# v0_1.net
KiCad netlist of a schematic drawn in EAGLE
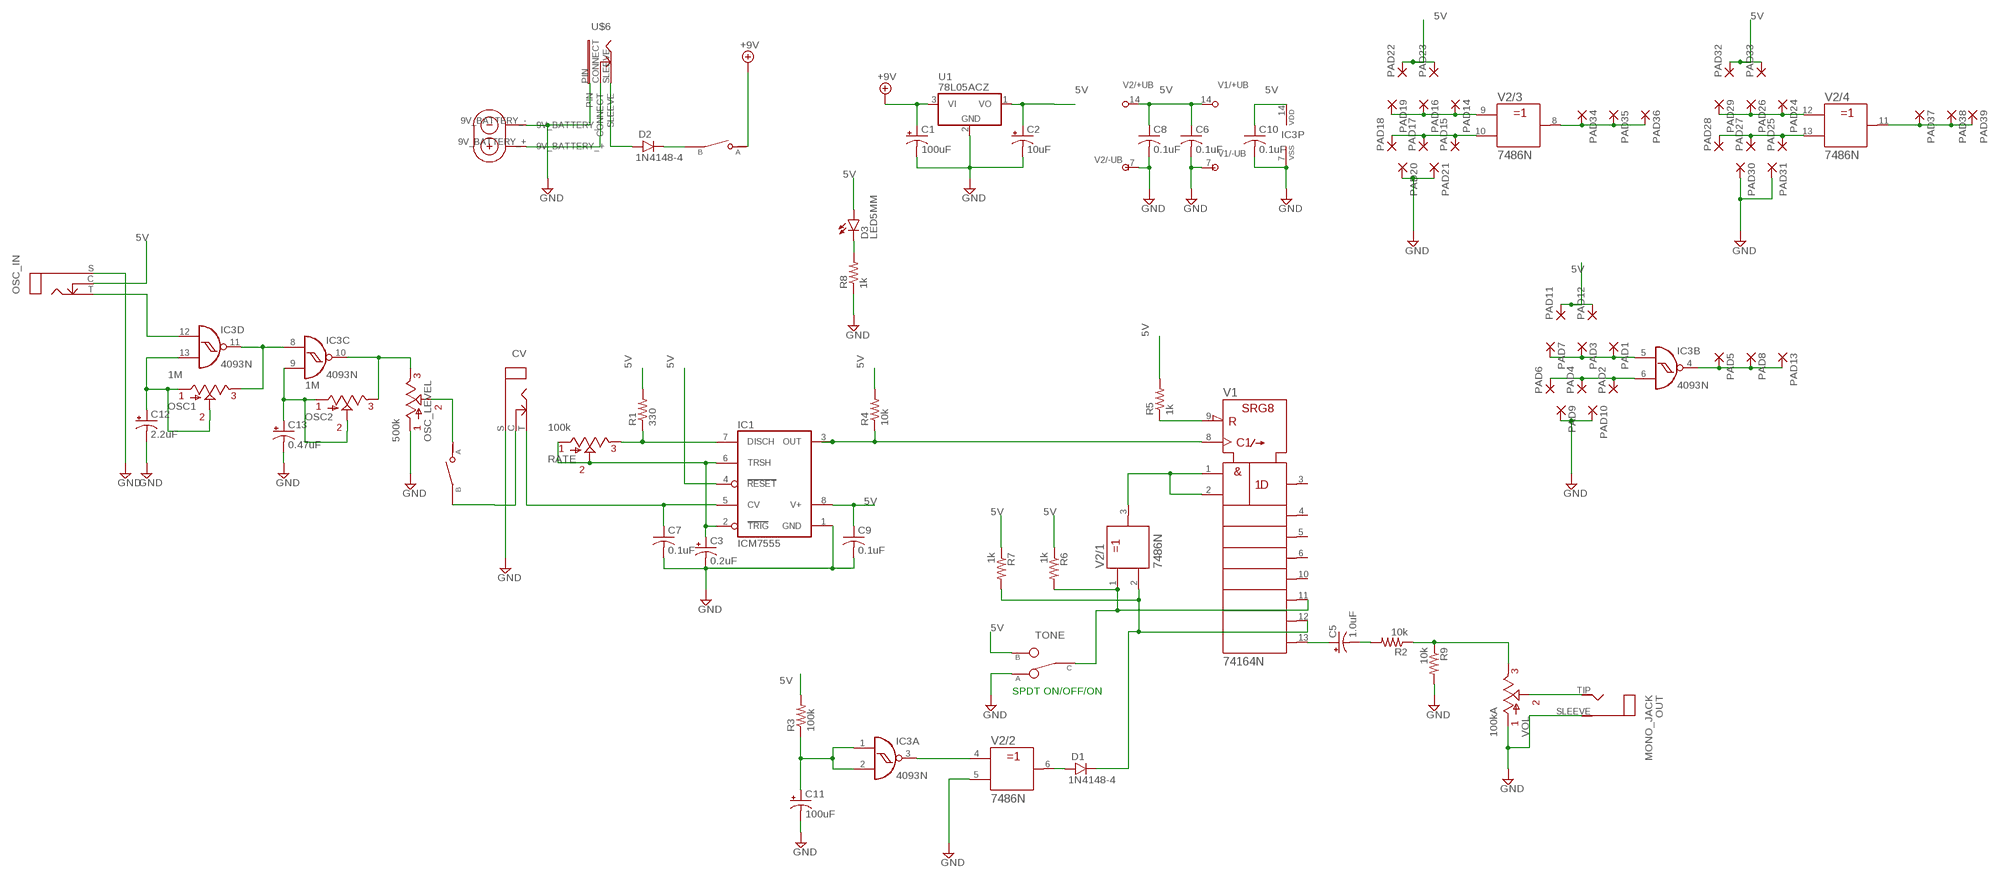
[diagram p0: schematic, sheet 1]

(export (version "E")
  (design (tool "Eeschema 10.0.6"))
  (components
    (comp (ref "C1")
      (value "100uF")
      (footprint "eagle-import:063_025")
      (libsource (lib "eagle-import") (part "0631"))
    )
    (comp (ref "C2")
      (value "10uF")
      (footprint "eagle-import:063_025")
      (libsource (lib "eagle-import") (part "0631"))
    )
    (comp (ref "C3")
      (value "0.2uF")
      (footprint "eagle-import:063_025")
      (libsource (lib "eagle-import") (part "0631"))
    )
    (comp (ref "C5")
      (value "1.0uF")
      (footprint "eagle-import:063_025")
      (libsource (lib "eagle-import") (part "0631"))
    )
    (comp (ref "C6")
      (value "0.1uF")
      (footprint "eagle-import:C050-030X075")
      (libsource (lib "eagle-import") (part "C-US050-030X075"))
    )
    (comp (ref "C7")
      (value "0.1uF")
      (footprint "eagle-import:C050-030X075")
      (libsource (lib "eagle-import") (part "C-US050-030X075"))
    )
    (comp (ref "C8")
      (value "0.1uF")
      (footprint "eagle-import:C050-030X075")
      (libsource (lib "eagle-import") (part "C-US050-030X075"))
    )
    (comp (ref "C9")
      (value "0.1uF")
      (footprint "eagle-import:C050-030X075")
      (libsource (lib "eagle-import") (part "C-US050-030X075"))
    )
    (comp (ref "C10")
      (value "0.1uF")
      (footprint "eagle-import:C050-030X075")
      (libsource (lib "eagle-import") (part "C-US050-030X075"))
    )
    (comp (ref "C11")
      (value "100uF")
      (footprint "eagle-import:063_025")
      (libsource (lib "eagle-import") (part "0631"))
    )
    (comp (ref "C12")
      (value "2.2uF")
      (footprint "eagle-import:063_025")
      (libsource (lib "eagle-import") (part "0631"))
    )
    (comp (ref "C13")
      (value "0.47uF")
      (footprint "eagle-import:063_025")
      (libsource (lib "eagle-import") (part "0631"))
    )
    (comp (ref "CV")
      (value "MONO_JACK_W_SHUNT")
      (footprint "eagle-import:MONO_JACK_W_SHUNT")
      (libsource (lib "eagle-import") (part "MONO_JACK_W_SHUNT"))
    )
    (comp (ref "CV+OSC_ON/OFF")
      (value "SPST_SWITCH")
      (footprint "eagle-import:SPST_TOGGLE_SWITCH")
      (libsource (lib "eagle-import") (part "SPST_SWITCH"))
    )
    (comp (ref "D1")
      (value "1N4148-4")
      (footprint "eagle-import:DO35-4")
      (libsource (lib "eagle-import") (part "1N4148-4"))
    )
    (comp (ref "D2")
      (value "1N4148-4")
      (footprint "eagle-import:DO35-4")
      (libsource (lib "eagle-import") (part "1N4148-4"))
    )
    (comp (ref "D3")
      (value "LED5MM")
      (footprint "eagle-import:LED5MM")
      (libsource (lib "eagle-import") (part "LED5MM"))
    )
    (comp (ref "IC1")
      (value "ICM7555")
      (footprint "eagle-import:DIL08")
      (libsource (lib "eagle-import") (part "ICM7555"))
    )
    (comp (ref "IC3")
      (value "4093N")
      (footprint "eagle-import:DIL14")
      (libsource (lib "eagle-import") (part "4093N"))
    )
    (comp (ref "ON/OFF")
      (value "SPST_SWITCH")
      (footprint "eagle-import:SPST_TOGGLE_SWITCH")
      (libsource (lib "eagle-import") (part "SPST_SWITCH"))
    )
    (comp (ref "OSC1")
      (value "1M")
      (footprint "eagle-import:POT")
      (libsource (lib "eagle-import") (part "POT"))
    )
    (comp (ref "OSC2")
      (value "1M")
      (footprint "eagle-import:POT")
      (libsource (lib "eagle-import") (part "POT"))
    )
    (comp (ref "OSC_IN")
      (value "MONO_JACK_W_SHUNT")
      (footprint "eagle-import:MONO_JACK_W_SHUNT")
      (libsource (lib "eagle-import") (part "MONO_JACK_W_SHUNT"))
    )
    (comp (ref "OSC_LEVEL")
      (value "500k")
      (footprint "eagle-import:POT")
      (libsource (lib "eagle-import") (part "POT"))
    )
    (comp (ref "OUT")
      (value "MONO_JACK")
      (footprint "eagle-import:MONO_JACK")
      (libsource (lib "eagle-import") (part "MONO_JACK"))
    )
    (comp (ref "PAD1")
      (value "WIREPAD1,6/0,9")
      (footprint "eagle-import:1,6_0,9")
      (libsource (lib "eagle-import") (part "WIREPAD1,6/0,9"))
    )
    (comp (ref "PAD2")
      (value "WIREPAD1,6/0,9")
      (footprint "eagle-import:1,6_0,9")
      (libsource (lib "eagle-import") (part "WIREPAD1,6/0,9"))
    )
    (comp (ref "PAD3")
      (value "WIREPAD1,6/0,9")
      (footprint "eagle-import:1,6_0,9")
      (libsource (lib "eagle-import") (part "WIREPAD1,6/0,9"))
    )
    (comp (ref "PAD4")
      (value "WIREPAD1,6/0,9")
      (footprint "eagle-import:1,6_0,9")
      (libsource (lib "eagle-import") (part "WIREPAD1,6/0,9"))
    )
    (comp (ref "PAD5")
      (value "WIREPAD1,6/0,9")
      (footprint "eagle-import:1,6_0,9")
      (libsource (lib "eagle-import") (part "WIREPAD1,6/0,9"))
    )
    (comp (ref "PAD6")
      (value "WIREPAD1,6/0,9")
      (footprint "eagle-import:1,6_0,9")
      (libsource (lib "eagle-import") (part "WIREPAD1,6/0,9"))
    )
    (comp (ref "PAD7")
      (value "WIREPAD1,6/0,9")
      (footprint "eagle-import:1,6_0,9")
      (libsource (lib "eagle-import") (part "WIREPAD1,6/0,9"))
    )
    (comp (ref "PAD8")
      (value "WIREPAD1,6/0,9")
      (footprint "eagle-import:1,6_0,9")
      (libsource (lib "eagle-import") (part "WIREPAD1,6/0,9"))
    )
    (comp (ref "PAD9")
      (value "WIREPAD1,6/0,9")
      (footprint "eagle-import:1,6_0,9")
      (libsource (lib "eagle-import") (part "WIREPAD1,6/0,9"))
    )
    (comp (ref "PAD10")
      (value "WIREPAD1,6/0,9")
      (footprint "eagle-import:1,6_0,9")
      (libsource (lib "eagle-import") (part "WIREPAD1,6/0,9"))
    )
    (comp (ref "PAD11")
      (value "WIREPAD1,6/0,9")
      (footprint "eagle-import:1,6_0,9")
      (libsource (lib "eagle-import") (part "WIREPAD1,6/0,9"))
    )
    (comp (ref "PAD12")
      (value "WIREPAD1,6/0,9")
      (footprint "eagle-import:1,6_0,9")
      (libsource (lib "eagle-import") (part "WIREPAD1,6/0,9"))
    )
    (comp (ref "PAD13")
      (value "WIREPAD1,6/0,9")
      (footprint "eagle-import:1,6_0,9")
      (libsource (lib "eagle-import") (part "WIREPAD1,6/0,9"))
    )
    (comp (ref "PAD14")
      (value "WIREPAD1,6/0,9")
      (footprint "eagle-import:1,6_0,9")
      (libsource (lib "eagle-import") (part "WIREPAD1,6/0,9"))
    )
    (comp (ref "PAD15")
      (value "WIREPAD1,6/0,9")
      (footprint "eagle-import:1,6_0,9")
      (libsource (lib "eagle-import") (part "WIREPAD1,6/0,9"))
    )
    (comp (ref "PAD16")
      (value "WIREPAD1,6/0,9")
      (footprint "eagle-import:1,6_0,9")
      (libsource (lib "eagle-import") (part "WIREPAD1,6/0,9"))
    )
    (comp (ref "PAD17")
      (value "WIREPAD1,6/0,9")
      (footprint "eagle-import:1,6_0,9")
      (libsource (lib "eagle-import") (part "WIREPAD1,6/0,9"))
    )
    (comp (ref "PAD18")
      (value "WIREPAD1,6/0,9")
      (footprint "eagle-import:1,6_0,9")
      (libsource (lib "eagle-import") (part "WIREPAD1,6/0,9"))
    )
    (comp (ref "PAD19")
      (value "WIREPAD1,6/0,9")
      (footprint "eagle-import:1,6_0,9")
      (libsource (lib "eagle-import") (part "WIREPAD1,6/0,9"))
    )
    (comp (ref "PAD20")
      (value "WIREPAD1,6/0,9")
      (footprint "eagle-import:1,6_0,9")
      (libsource (lib "eagle-import") (part "WIREPAD1,6/0,9"))
    )
    (comp (ref "PAD21")
      (value "WIREPAD1,6/0,9")
      (footprint "eagle-import:1,6_0,9")
      (libsource (lib "eagle-import") (part "WIREPAD1,6/0,9"))
    )
    (comp (ref "PAD22")
      (value "WIREPAD1,6/0,9")
      (footprint "eagle-import:1,6_0,9")
      (libsource (lib "eagle-import") (part "WIREPAD1,6/0,9"))
    )
    (comp (ref "PAD23")
      (value "WIREPAD1,6/0,9")
      (footprint "eagle-import:1,6_0,9")
      (libsource (lib "eagle-import") (part "WIREPAD1,6/0,9"))
    )
    (comp (ref "PAD24")
      (value "WIREPAD1,6/0,9")
      (footprint "eagle-import:1,6_0,9")
      (libsource (lib "eagle-import") (part "WIREPAD1,6/0,9"))
    )
    (comp (ref "PAD25")
      (value "WIREPAD1,6/0,9")
      (footprint "eagle-import:1,6_0,9")
      (libsource (lib "eagle-import") (part "WIREPAD1,6/0,9"))
    )
    (comp (ref "PAD26")
      (value "WIREPAD1,6/0,9")
      (footprint "eagle-import:1,6_0,9")
      (libsource (lib "eagle-import") (part "WIREPAD1,6/0,9"))
    )
    (comp (ref "PAD27")
      (value "WIREPAD1,6/0,9")
      (footprint "eagle-import:1,6_0,9")
      (libsource (lib "eagle-import") (part "WIREPAD1,6/0,9"))
    )
    (comp (ref "PAD28")
      (value "WIREPAD1,6/0,9")
      (footprint "eagle-import:1,6_0,9")
      (libsource (lib "eagle-import") (part "WIREPAD1,6/0,9"))
    )
    (comp (ref "PAD29")
      (value "WIREPAD1,6/0,9")
      (footprint "eagle-import:1,6_0,9")
      (libsource (lib "eagle-import") (part "WIREPAD1,6/0,9"))
    )
    (comp (ref "PAD30")
      (value "WIREPAD1,6/0,9")
      (footprint "eagle-import:1,6_0,9")
      (libsource (lib "eagle-import") (part "WIREPAD1,6/0,9"))
    )
    (comp (ref "PAD31")
      (value "WIREPAD1,6/0,9")
      (footprint "eagle-import:1,6_0,9")
      (libsource (lib "eagle-import") (part "WIREPAD1,6/0,9"))
    )
    (comp (ref "PAD32")
      (value "WIREPAD1,6/0,9")
      (footprint "eagle-import:1,6_0,9")
      (libsource (lib "eagle-import") (part "WIREPAD1,6/0,9"))
    )
    (comp (ref "PAD33")
      (value "WIREPAD1,6/0,9")
      (footprint "eagle-import:1,6_0,9")
      (libsource (lib "eagle-import") (part "WIREPAD1,6/0,9"))
    )
    (comp (ref "PAD34")
      (value "WIREPAD1,6/0,9")
      (footprint "eagle-import:1,6_0,9")
      (libsource (lib "eagle-import") (part "WIREPAD1,6/0,9"))
    )
    (comp (ref "PAD35")
      (value "WIREPAD1,6/0,9")
      (footprint "eagle-import:1,6_0,9")
      (libsource (lib "eagle-import") (part "WIREPAD1,6/0,9"))
    )
    (comp (ref "PAD36")
      (value "WIREPAD1,6/0,9")
      (footprint "eagle-import:1,6_0,9")
      (libsource (lib "eagle-import") (part "WIREPAD1,6/0,9"))
    )
    (comp (ref "PAD37")
      (value "WIREPAD1,6/0,9")
      (footprint "eagle-import:1,6_0,9")
      (libsource (lib "eagle-import") (part "WIREPAD1,6/0,9"))
    )
    (comp (ref "PAD38")
      (value "WIREPAD1,6/0,9")
      (footprint "eagle-import:1,6_0,9")
      (libsource (lib "eagle-import") (part "WIREPAD1,6/0,9"))
    )
    (comp (ref "PAD39")
      (value "WIREPAD1,6/0,9")
      (footprint "eagle-import:1,6_0,9")
      (libsource (lib "eagle-import") (part "WIREPAD1,6/0,9"))
    )
    (comp (ref "R1")
      (value "330")
      (footprint "eagle-import:R0207_4")
      (libsource (lib "eagle-import") (part "6MM.4"))
    )
    (comp (ref "R2")
      (value "10k")
      (footprint "eagle-import:R0207_4")
      (libsource (lib "eagle-import") (part "6MM.4"))
    )
    (comp (ref "R3")
      (value "100k")
      (footprint "eagle-import:R0207_4")
      (libsource (lib "eagle-import") (part "6MM.4"))
    )
    (comp (ref "R4")
      (value "10k")
      (footprint "eagle-import:R0207_4")
      (libsource (lib "eagle-import") (part "6MM.4"))
    )
    (comp (ref "R5")
      (value "1k")
      (footprint "eagle-import:R0207_4")
      (libsource (lib "eagle-import") (part "6MM.4"))
    )
    (comp (ref "R6")
      (value "1k")
      (footprint "eagle-import:R0207_4")
      (libsource (lib "eagle-import") (part "6MM.4"))
    )
    (comp (ref "R7")
      (value "1k")
      (footprint "eagle-import:R0207_4")
      (libsource (lib "eagle-import") (part "6MM.4"))
    )
    (comp (ref "R8")
      (value "1k")
      (footprint "eagle-import:R0207_4")
      (libsource (lib "eagle-import") (part "6MM.4"))
    )
    (comp (ref "R9")
      (value "10k")
      (footprint "eagle-import:R0207_4")
      (libsource (lib "eagle-import") (part "6MM.4"))
    )
    (comp (ref "RATE")
      (value "100k")
      (footprint "eagle-import:POT")
      (libsource (lib "eagle-import") (part "POT"))
    )
    (comp (ref "TONE")
      (value "SPDT_SWITCH")
      (footprint "eagle-import:SPDT_TOGGLE_SWITCH")
      (libsource (lib "eagle-import") (part "SPDT_SWITCH"))
    )
    (comp (ref "U$6")
      (value "DC_JACK_OFFBOARD")
      (footprint "eagle-import:DC_JACK_OFFBOARD")
      (libsource (lib "eagle-import") (part "DC_JACK_OFFBOARD"))
    )
    (comp (ref "U$7")
      (value "9V_BATTERY_CLIP")
      (footprint "eagle-import:9V_BATTERY")
      (libsource (lib "eagle-import") (part "9V_BATTERY_CLIP"))
    )
    (comp (ref "U1")
      (value "78L05ACZ")
      (footprint "eagle-import:TO-92")
      (libsource (lib "eagle-import") (part "78L05ACZ"))
    )
    (comp (ref "V1")
      (value "74164N")
      (footprint "eagle-import:DIL14")
      (libsource (lib "eagle-import") (part "74164N"))
    )
    (comp (ref "V2")
      (value "7486N")
      (footprint "eagle-import:DIL14")
      (libsource (lib "eagle-import") (part "7486N"))
    )
    (comp (ref "VOL")
      (value "100kA")
      (footprint "eagle-import:POT")
      (libsource (lib "eagle-import") (part "POT"))
    )
  )
  (nets
    (net (code "1") (name "+9V") (class "Default")
      (node (ref "C1") (pin "+") (pinfunction "+_+") (pintype "passive"))
      (node (ref "ON/OFF") (pin "A") (pinfunction "A_A") (pintype "passive"))
      (node (ref "U1") (pin "3") (pinfunction "VI_3") (pintype "input"))
    )
    (net (code "2") (name "/5V") (class "Default")
      (node (ref "C10") (pin "1") (pinfunction "1_1") (pintype "passive"))
      (node (ref "C2") (pin "+") (pinfunction "+_+") (pintype "passive"))
      (node (ref "C6") (pin "1") (pinfunction "1_1") (pintype "passive"))
      (node (ref "C8") (pin "1") (pinfunction "1_1") (pintype "passive"))
      (node (ref "C9") (pin "1") (pinfunction "1_1") (pintype "passive"))
      (node (ref "D3") (pin "A") (pinfunction "A_A") (pintype "passive"))
      (node (ref "IC1") (pin "4") (pinfunction "RESET_4") (pintype "input"))
      (node (ref "IC1") (pin "8") (pinfunction "V+_8") (pintype "power_in"))
      (node (ref "IC3") (pin "14") (pinfunction "VDD_14") (pintype "power_in"))
      (node (ref "OSC_IN") (pin "C") (pinfunction "CONNECT_C") (pintype "passive"))
      (node (ref "PAD11") (pin "1") (pinfunction "P_1") (pintype "passive"))
      (node (ref "PAD12") (pin "1") (pinfunction "P_1") (pintype "passive"))
      (node (ref "PAD22") (pin "1") (pinfunction "P_1") (pintype "passive"))
      (node (ref "PAD23") (pin "1") (pinfunction "P_1") (pintype "passive"))
      (node (ref "PAD32") (pin "1") (pinfunction "P_1") (pintype "passive"))
      (node (ref "PAD33") (pin "1") (pinfunction "P_1") (pintype "passive"))
      (node (ref "R1") (pin "2") (pinfunction "2_2") (pintype "passive"))
      (node (ref "R3") (pin "2") (pinfunction "2_2") (pintype "passive"))
      (node (ref "R4") (pin "2") (pinfunction "2_2") (pintype "passive"))
      (node (ref "R5") (pin "2") (pinfunction "2_2") (pintype "passive"))
      (node (ref "R6") (pin "1") (pinfunction "1_1") (pintype "passive"))
      (node (ref "R7") (pin "1") (pinfunction "1_1") (pintype "passive"))
      (node (ref "TONE") (pin "B") (pinfunction "B_B") (pintype "passive"))
      (node (ref "U1") (pin "1") (pinfunction "VO_1") (pintype "passive"))
      (node (ref "V1") (pin "14") (pinfunction "+UB_14") (pintype "power_in"))
      (node (ref "V2") (pin "14") (pinfunction "+UB_14") (pintype "power_in"))
    )
    (net (code "3") (name "GND") (class "Default")
      (node (ref "C1") (pin "-") (pinfunction "-_-") (pintype "passive"))
      (node (ref "C10") (pin "2") (pinfunction "2_2") (pintype "passive"))
      (node (ref "C11") (pin "-") (pinfunction "-_-") (pintype "passive"))
      (node (ref "C12") (pin "-") (pinfunction "-_-") (pintype "passive"))
      (node (ref "C13") (pin "-") (pinfunction "-_-") (pintype "passive"))
      (node (ref "C2") (pin "-") (pinfunction "-_-") (pintype "passive"))
      (node (ref "C3") (pin "-") (pinfunction "-_-") (pintype "passive"))
      (node (ref "C6") (pin "2") (pinfunction "2_2") (pintype "passive"))
      (node (ref "C7") (pin "2") (pinfunction "2_2") (pintype "passive"))
      (node (ref "C8") (pin "2") (pinfunction "2_2") (pintype "passive"))
      (node (ref "C9") (pin "2") (pinfunction "2_2") (pintype "passive"))
      (node (ref "CV") (pin "S") (pinfunction "SLEEVE_S") (pintype "passive"))
      (node (ref "IC1") (pin "1") (pinfunction "GND_1") (pintype "power_in"))
      (node (ref "IC3") (pin "7") (pinfunction "VSS_7") (pintype "power_in"))
      (node (ref "OSC_IN") (pin "S") (pinfunction "SLEEVE_S") (pintype "passive"))
      (node (ref "OSC_LEVEL") (pin "1") (pinfunction "1_1") (pintype "passive"))
      (node (ref "OUT") (pin "SLEEVE") (pinfunction "SLEEVE_SLEEVE") (pintype "passive"))
      (node (ref "PAD10") (pin "1") (pinfunction "P_1") (pintype "passive"))
      (node (ref "PAD20") (pin "1") (pinfunction "P_1") (pintype "passive"))
      (node (ref "PAD21") (pin "1") (pinfunction "P_1") (pintype "passive"))
      (node (ref "PAD30") (pin "1") (pinfunction "P_1") (pintype "passive"))
      (node (ref "PAD31") (pin "1") (pinfunction "P_1") (pintype "passive"))
      (node (ref "PAD9") (pin "1") (pinfunction "P_1") (pintype "passive"))
      (node (ref "R8") (pin "1") (pinfunction "1_1") (pintype "passive"))
      (node (ref "R9") (pin "2") (pinfunction "2_2") (pintype "passive"))
      (node (ref "TONE") (pin "A") (pinfunction "A_A") (pintype "passive"))
      (node (ref "U$6") (pin "PIN") (pinfunction "PIN_PIN") (pintype "bidirectional"))
      (node (ref "U$7") (pin "9V_BATTERY_-") (pinfunction "9V_BATTERY_-_9V_BATTERY_-") (pintype "power_in"))
      (node (ref "U1") (pin "2") (pinfunction "GND_2") (pintype "passive"))
      (node (ref "V1") (pin "7") (pinfunction "-UB_7") (pintype "power_in"))
      (node (ref "V2") (pin "5") (pinfunction "B_5") (pintype "input"))
      (node (ref "V2") (pin "7") (pinfunction "-UB_7") (pintype "power_in"))
      (node (ref "VOL") (pin "1") (pinfunction "1_1") (pintype "passive"))
    )
    (net (code "4") (name "Net-(C5-Pad-)") (class "Default")
      (node (ref "C5") (pin "-") (pinfunction "-_-") (pintype "passive"))
      (node (ref "R2") (pin "2") (pinfunction "2_2") (pintype "passive"))
    )
    (net (code "5") (name "Net-(CV+OSC_ON/OFF-PadA)") (class "Default")
      (node (ref "CV+OSC_ON/OFF") (pin "A") (pinfunction "A_A") (pintype "passive"))
      (node (ref "OSC_LEVEL") (pin "2") (pinfunction "2_2") (pintype "passive"))
    )
    (net (code "6") (name "Net-(CV-CONNECT)") (class "Default")
      (node (ref "CV") (pin "C") (pinfunction "CONNECT_C") (pintype "passive"))
      (node (ref "CV+OSC_ON/OFF") (pin "B") (pinfunction "B_B") (pintype "passive"))
    )
    (net (code "7") (name "Net-(CV-TIP)") (class "Default")
      (node (ref "C7") (pin "1") (pinfunction "1_1") (pintype "passive"))
      (node (ref "CV") (pin "T") (pinfunction "TIP_T") (pintype "passive"))
      (node (ref "IC1") (pin "5") (pinfunction "CV_5") (pintype "passive"))
    )
    (net (code "8") (name "Net-(D2-PadA)") (class "Default")
      (node (ref "D2") (pin "A") (pinfunction "A_A") (pintype "passive"))
      (node (ref "U$6") (pin "SLEEVE") (pinfunction "SLEEVE_SLEEVE") (pintype "bidirectional"))
    )
    (net (code "9") (name "Net-(D2-PadC)") (class "Default")
      (node (ref "D2") (pin "C") (pinfunction "C_C") (pintype "passive"))
      (node (ref "ON/OFF") (pin "B") (pinfunction "B_B") (pintype "passive"))
    )
    (net (code "10") (name "Net-(D3-C)") (class "Default")
      (node (ref "D3") (pin "K") (pinfunction "C_K") (pintype "passive"))
      (node (ref "R8") (pin "2") (pinfunction "2_2") (pintype "passive"))
    )
    (net (code "11") (name "Net-(IC1-DISCH)") (class "Default")
      (node (ref "IC1") (pin "7") (pinfunction "DISCH_7") (pintype "input"))
      (node (ref "R1") (pin "1") (pinfunction "1_1") (pintype "passive"))
      (node (ref "RATE") (pin "3") (pinfunction "3_3") (pintype "passive"))
    )
    (net (code "12") (name "Net-(IC1-OUT)") (class "Default")
      (node (ref "IC1") (pin "3") (pinfunction "OUT_3") (pintype "output"))
      (node (ref "R4") (pin "1") (pinfunction "1_1") (pintype "passive"))
      (node (ref "V1") (pin "8") (pinfunction "CLK_8") (pintype "input"))
    )
    (net (code "13") (name "Net-(IC1-TRIG)") (class "Default")
      (node (ref "C3") (pin "+") (pinfunction "+_+") (pintype "passive"))
      (node (ref "IC1") (pin "2") (pinfunction "TRIG_2") (pintype "bidirectional"))
      (node (ref "IC1") (pin "6") (pinfunction "TRSH_6") (pintype "input"))
      (node (ref "RATE") (pin "1") (pinfunction "1_1") (pintype "passive"))
      (node (ref "RATE") (pin "2") (pinfunction "2_2") (pintype "passive"))
    )
    (net (code "14") (name "Net-(IC3A-I0)") (class "Default")
      (node (ref "C11") (pin "+") (pinfunction "+_+") (pintype "passive"))
      (node (ref "IC3") (pin "1") (pinfunction "I0_1") (pintype "input"))
      (node (ref "IC3") (pin "2") (pinfunction "I1_2") (pintype "input"))
      (node (ref "R3") (pin "1") (pinfunction "1_1") (pintype "passive"))
    )
    (net (code "15") (name "Net-(IC3A-O)") (class "Default")
      (node (ref "IC3") (pin "3") (pinfunction "O_3") (pintype "output"))
      (node (ref "V2") (pin "4") (pinfunction "A_4") (pintype "input"))
    )
    (net (code "16") (name "Net-(IC3B-I0)") (class "Default")
      (node (ref "IC3") (pin "5") (pinfunction "I0_5") (pintype "input"))
      (node (ref "PAD1") (pin "1") (pinfunction "P_1") (pintype "passive"))
      (node (ref "PAD3") (pin "1") (pinfunction "P_1") (pintype "passive"))
      (node (ref "PAD7") (pin "1") (pinfunction "P_1") (pintype "passive"))
    )
    (net (code "17") (name "Net-(IC3B-I1)") (class "Default")
      (node (ref "IC3") (pin "6") (pinfunction "I1_6") (pintype "input"))
      (node (ref "PAD2") (pin "1") (pinfunction "P_1") (pintype "passive"))
      (node (ref "PAD4") (pin "1") (pinfunction "P_1") (pintype "passive"))
      (node (ref "PAD6") (pin "1") (pinfunction "P_1") (pintype "passive"))
    )
    (net (code "18") (name "Net-(IC3B-O)") (class "Default")
      (node (ref "IC3") (pin "4") (pinfunction "O_4") (pintype "output"))
      (node (ref "PAD13") (pin "1") (pinfunction "P_1") (pintype "passive"))
      (node (ref "PAD5") (pin "1") (pinfunction "P_1") (pintype "passive"))
      (node (ref "PAD8") (pin "1") (pinfunction "P_1") (pintype "passive"))
    )
    (net (code "19") (name "Net-(IC3C-I0)") (class "Default")
      (node (ref "IC3") (pin "11") (pinfunction "O_11") (pintype "output"))
      (node (ref "IC3") (pin "8") (pinfunction "I0_8") (pintype "input"))
      (node (ref "OSC1") (pin "3") (pinfunction "3_3") (pintype "passive"))
    )
    (net (code "20") (name "Net-(IC3C-I1)") (class "Default")
      (node (ref "C13") (pin "+") (pinfunction "+_+") (pintype "passive"))
      (node (ref "IC3") (pin "9") (pinfunction "I1_9") (pintype "input"))
      (node (ref "OSC2") (pin "1") (pinfunction "1_1") (pintype "passive"))
      (node (ref "OSC2") (pin "2") (pinfunction "2_2") (pintype "passive"))
    )
    (net (code "21") (name "Net-(IC3C-O)") (class "Default")
      (node (ref "IC3") (pin "10") (pinfunction "O_10") (pintype "output"))
      (node (ref "OSC2") (pin "3") (pinfunction "3_3") (pintype "passive"))
      (node (ref "OSC_LEVEL") (pin "3") (pinfunction "3_3") (pintype "passive"))
    )
    (net (code "22") (name "Net-(IC3D-I0)") (class "Default")
      (node (ref "IC3") (pin "12") (pinfunction "I0_12") (pintype "input"))
      (node (ref "OSC_IN") (pin "T") (pinfunction "TIP_T") (pintype "passive"))
    )
    (net (code "23") (name "Net-(IC3D-I1)") (class "Default")
      (node (ref "C12") (pin "+") (pinfunction "+_+") (pintype "passive"))
      (node (ref "IC3") (pin "13") (pinfunction "I1_13") (pintype "input"))
      (node (ref "OSC1") (pin "1") (pinfunction "1_1") (pintype "passive"))
      (node (ref "OSC1") (pin "2") (pinfunction "2_2") (pintype "passive"))
    )
    (net (code "24") (name "Net-(OUT-PadTIP)") (class "Default")
      (node (ref "OUT") (pin "TIP") (pinfunction "TIP_TIP") (pintype "passive"))
      (node (ref "VOL") (pin "2") (pinfunction "2_2") (pintype "passive"))
    )
    (net (code "25") (name "Net-(PAD14-P)") (class "Default")
      (node (ref "PAD14") (pin "1") (pinfunction "P_1") (pintype "passive"))
      (node (ref "PAD16") (pin "1") (pinfunction "P_1") (pintype "passive"))
      (node (ref "PAD19") (pin "1") (pinfunction "P_1") (pintype "passive"))
      (node (ref "V2") (pin "9") (pinfunction "A_9") (pintype "input"))
    )
    (net (code "26") (name "Net-(PAD15-P)") (class "Default")
      (node (ref "PAD15") (pin "1") (pinfunction "P_1") (pintype "passive"))
      (node (ref "PAD17") (pin "1") (pinfunction "P_1") (pintype "passive"))
      (node (ref "PAD18") (pin "1") (pinfunction "P_1") (pintype "passive"))
      (node (ref "V2") (pin "10") (pinfunction "B_10") (pintype "input"))
    )
    (net (code "27") (name "Net-(PAD24-P)") (class "Default")
      (node (ref "PAD24") (pin "1") (pinfunction "P_1") (pintype "passive"))
      (node (ref "PAD26") (pin "1") (pinfunction "P_1") (pintype "passive"))
      (node (ref "PAD29") (pin "1") (pinfunction "P_1") (pintype "passive"))
      (node (ref "V2") (pin "12") (pinfunction "A_12") (pintype "input"))
    )
    (net (code "28") (name "Net-(PAD25-P)") (class "Default")
      (node (ref "PAD25") (pin "1") (pinfunction "P_1") (pintype "passive"))
      (node (ref "PAD27") (pin "1") (pinfunction "P_1") (pintype "passive"))
      (node (ref "PAD28") (pin "1") (pinfunction "P_1") (pintype "passive"))
      (node (ref "V2") (pin "13") (pinfunction "B_13") (pintype "input"))
    )
    (net (code "29") (name "Net-(PAD34-P)") (class "Default")
      (node (ref "PAD34") (pin "1") (pinfunction "P_1") (pintype "passive"))
      (node (ref "PAD35") (pin "1") (pinfunction "P_1") (pintype "passive"))
      (node (ref "PAD36") (pin "1") (pinfunction "P_1") (pintype "passive"))
      (node (ref "V2") (pin "8") (pinfunction "Y_8") (pintype "output"))
    )
    (net (code "30") (name "Net-(PAD37-P)") (class "Default")
      (node (ref "PAD37") (pin "1") (pinfunction "P_1") (pintype "passive"))
      (node (ref "PAD38") (pin "1") (pinfunction "P_1") (pintype "passive"))
      (node (ref "PAD39") (pin "1") (pinfunction "P_1") (pintype "passive"))
      (node (ref "V2") (pin "11") (pinfunction "Y_11") (pintype "output"))
    )
    (net (code "31") (name "Net-(R2-Pad1)") (class "Default")
      (node (ref "R2") (pin "1") (pinfunction "1_1") (pintype "passive"))
      (node (ref "R9") (pin "1") (pinfunction "1_1") (pintype "passive"))
      (node (ref "VOL") (pin "3") (pinfunction "3_3") (pintype "passive"))
    )
    (net (code "32") (name "Net-(U$6-PadCONNECT)") (class "Default")
      (node (ref "U$6") (pin "CONNECT") (pinfunction "CONNECT_CONNECT") (pintype "bidirectional"))
      (node (ref "U$7") (pin "9V_BATTERY_+") (pinfunction "9V_BATTERY_+_9V_BATTERY_+") (pintype "power_in"))
    )
    (net (code "33") (name "Net-(V1C-A)") (class "Default")
      (node (ref "V1") (pin "1") (pinfunction "A_1") (pintype "input"))
      (node (ref "V1") (pin "2") (pinfunction "B_2") (pintype "input"))
      (node (ref "V2") (pin "3") (pinfunction "Y_3") (pintype "output"))
    )
    (net (code "34") (name "Net-(V1C-QF)") (class "Default")
      (node (ref "R6") (pin "2") (pinfunction "2_2") (pintype "passive"))
      (node (ref "TONE") (pin "C") (pinfunction "C_C") (pintype "passive"))
      (node (ref "V1") (pin "11") (pinfunction "QF_11") (pintype "output"))
      (node (ref "V2") (pin "1") (pinfunction "A_1") (pintype "input"))
    )
    (net (code "35") (name "Net-(V1C-QG)") (class "Default")
      (node (ref "D1") (pin "C") (pinfunction "C_C") (pintype "passive"))
      (node (ref "R7") (pin "2") (pinfunction "2_2") (pintype "passive"))
      (node (ref "V1") (pin "12") (pinfunction "QG_12") (pintype "output"))
      (node (ref "V2") (pin "2") (pinfunction "B_2") (pintype "input"))
    )
    (net (code "36") (name "Net-(V1C-QH)") (class "Default")
      (node (ref "C5") (pin "+") (pinfunction "+_+") (pintype "passive"))
      (node (ref "V1") (pin "13") (pinfunction "QH_13") (pintype "output"))
    )
    (net (code "37") (name "Net-(V1C-~{CLR})") (class "Default")
      (node (ref "R5") (pin "1") (pinfunction "1_1") (pintype "passive"))
      (node (ref "V1") (pin "9") (pinfunction "~{CLR}_9") (pintype "input"))
    )
    (net (code "38") (name "Net-(V2D-Y)") (class "Default")
      (node (ref "D1") (pin "A") (pinfunction "A_A") (pintype "passive"))
      (node (ref "V2") (pin "6") (pinfunction "Y_6") (pintype "output"))
    )
    (net (code "39") (name "unconnected-(V1C-QA-Pad3)") (class "Default")
      (node (ref "V1") (pin "3") (pinfunction "QA_3") (pintype "output"))
    )
    (net (code "40") (name "unconnected-(V1C-QB-Pad4)") (class "Default")
      (node (ref "V1") (pin "4") (pinfunction "QB_4") (pintype "output"))
    )
    (net (code "41") (name "unconnected-(V1C-QC-Pad5)") (class "Default")
      (node (ref "V1") (pin "5") (pinfunction "QC_5") (pintype "output"))
    )
    (net (code "42") (name "unconnected-(V1C-QD-Pad6)") (class "Default")
      (node (ref "V1") (pin "6") (pinfunction "QD_6") (pintype "output"))
    )
    (net (code "43") (name "unconnected-(V1C-QE-Pad10)") (class "Default")
      (node (ref "V1") (pin "10") (pinfunction "QE_10") (pintype "output"))
    )
  )
)
